# Tastendruckverl_ngerer_1a.net
KiCad netlist of a schematic drawn in EAGLE
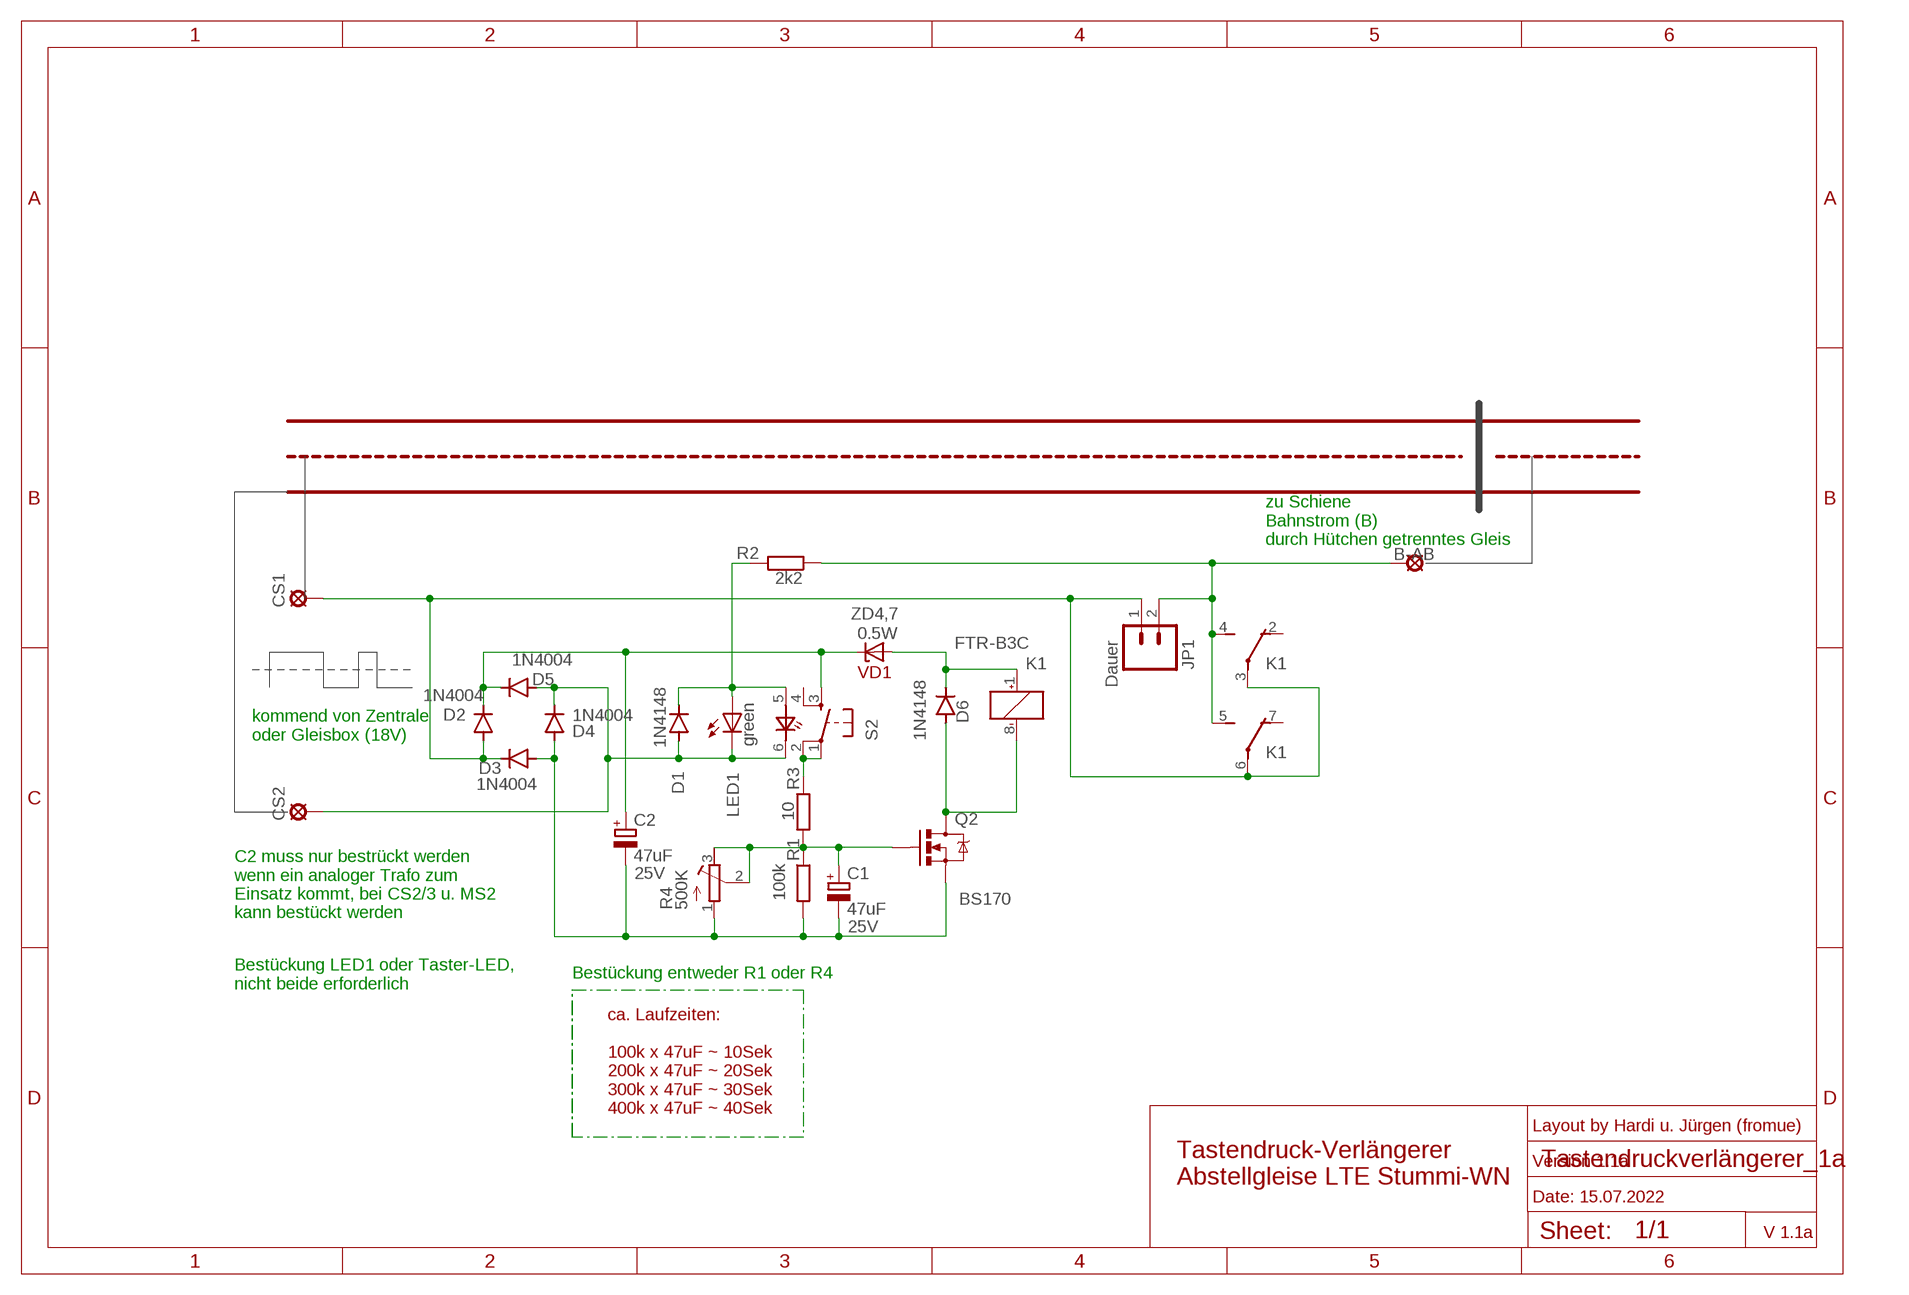
[diagram p0: schematic, sheet 1]

(export (version "E")
  (design (tool "Eeschema 10.0.6"))
  (components
    (comp (ref "B-AB")
      (value "SE14")
      (footprint "eagle-import:SE14")
      (libsource (lib "eagle-import") (part "SE14"))
    )
    (comp (ref "C1")
      (value "47uF")
      (footprint "eagle-import:TT2D5L")
      (fields (field (name "ADD") "25V"))
      (libsource (lib "eagle-import") (part "CPOL-EUTT2D5L"))
    )
    (comp (ref "C2")
      (value "47uF")
      (footprint "eagle-import:TT2D5L")
      (fields (field (name "ADD") "25V"))
      (libsource (lib "eagle-import") (part "CPOL-EUTT2D5L"))
    )
    (comp (ref "CS1")
      (value "SE14")
      (footprint "eagle-import:SE14")
      (libsource (lib "eagle-import") (part "SE14"))
    )
    (comp (ref "CS2")
      (value "SE14")
      (footprint "eagle-import:SE14")
      (libsource (lib "eagle-import") (part "SE14"))
    )
    (comp (ref "D1")
      (value "1N4148")
      (footprint "eagle-import:DO35-7")
      (fields (field (name "SPICEPREFIX") "D"))
      (libsource (lib "eagle-import") (part "1N4148DO35-7"))
    )
    (comp (ref "D2")
      (value "1N4004")
      (footprint "eagle-import:DO41-10A")
      (libsource (lib "eagle-import") (part "1N4004DO41-10A"))
    )
    (comp (ref "D3")
      (value "1N4004")
      (footprint "eagle-import:DO41-10A")
      (libsource (lib "eagle-import") (part "1N4004DO41-10A"))
    )
    (comp (ref "D4")
      (value "1N4004")
      (footprint "eagle-import:DO41-10A")
      (libsource (lib "eagle-import") (part "1N4004DO41-10A"))
    )
    (comp (ref "D5")
      (value "1N4004")
      (footprint "eagle-import:DO41-10A")
      (libsource (lib "eagle-import") (part "1N4004DO41-10A"))
    )
    (comp (ref "D6")
      (value "1N4148")
      (footprint "eagle-import:DO35-7")
      (fields (field (name "SPICEPREFIX") "D"))
      (libsource (lib "eagle-import") (part "1N4148DO35-7"))
    )
    (comp (ref "JP1")
      (value "Dauer")
      (footprint "eagle-import:1X02")
      (libsource (lib "eagle-import") (part "M02PTH"))
    )
    (comp (ref "K1")
      (value "FTR-B3C")
      (footprint "eagle-import:FTR-B4C")
      (libsource (lib "eagle-import") (part "FTR-B3C"))
    )
    (comp (ref "LED1")
      (value "green")
      (footprint "eagle-import:LED3MM")
      (libsource (lib "eagle-import") (part "LED3MM"))
    )
    (comp (ref "Q2")
      (value "BS170")
      (footprint "eagle-import:TO-92")
      (libsource (lib "eagle-import") (part "MOSFET-NCHANNELBS170"))
    )
    (comp (ref "R1")
      (value "100k")
      (footprint "eagle-import:0204_7")
      (libsource (lib "eagle-import") (part "R0204/7"))
    )
    (comp (ref "R2")
      (value "2k2")
      (footprint "eagle-import:0204_7")
      (fields (field (name "SPICEPREFIX") "4k7"))
      (libsource (lib "eagle-import") (part "R0204/7"))
    )
    (comp (ref "R3")
      (value "10")
      (footprint "eagle-import:0204_7")
      (libsource (lib "eagle-import") (part "R0204/7"))
    )
    (comp (ref "R4")
      (value "500K")
      (footprint "eagle-import:RTRIM3296W")
      (libsource (lib "eagle-import") (part "R-TRIMM3296W"))
    )
    (comp (ref "S2")
      (value "TASTER_LEDTC-1198-B")
      (footprint "eagle-import:TASTER_LED")
      (libsource (lib "eagle-import") (part "TASTER_LEDTC-1198-B"))
    )
    (comp (ref "VD1")
      (value "ZD4,7")
      (footprint "eagle-import:DIODES-ZENER_DO35-7")
      (fields (field (name "MOUSER") "ZF4.7") (field (name "POWER") "0.5W"))
      (libsource (lib "eagle-import") (part "DIODES-ZENER_?5.6V(1N5232)"))
    )
  )
  (nets
    (net (code "1") (name "Net-(K1A-P)") (class "Default")
      (node (ref "CS1") (pin "MP") (pinfunction "MP_MP") (pintype "passive"))
      (node (ref "D2") (pin "A") (pinfunction "A_A") (pintype "passive"))
      (node (ref "D3") (pin "C") (pinfunction "C_C") (pintype "passive"))
      (node (ref "JP1") (pin "1") (pinfunction "1_1") (pintype "passive"))
      (node (ref "K1") (pin "3") (pinfunction "P_3") (pintype "passive"))
      (node (ref "K1") (pin "6") (pinfunction "P_6") (pintype "passive"))
    )
    (net (code "2") (name "Net-(K1A-S)") (class "Default")
      (node (ref "B-AB") (pin "MP") (pinfunction "MP_MP") (pintype "passive"))
      (node (ref "JP1") (pin "2") (pinfunction "2_2") (pintype "passive"))
      (node (ref "K1") (pin "4") (pinfunction "S_4") (pintype "passive"))
      (node (ref "K1") (pin "5") (pinfunction "S_5") (pintype "passive"))
      (node (ref "R2") (pin "1") (pinfunction "1_1") (pintype "passive"))
    )
    (net (code "3") (name "Net-(K1C-+)") (class "Default")
      (node (ref "D6") (pin "C") (pinfunction "C_C") (pintype "passive"))
      (node (ref "K1") (pin "1") (pinfunction "+_1") (pintype "passive"))
      (node (ref "VD1") (pin "A") (pinfunction "A_A") (pintype "passive"))
    )
    (net (code "4") (name "Net-(K1C--)") (class "Default")
      (node (ref "D6") (pin "A") (pinfunction "A_A") (pintype "passive"))
      (node (ref "K1") (pin "8") (pinfunction "-_8") (pintype "passive"))
      (node (ref "Q2") (pin "1") (pinfunction "D_1") (pintype "passive"))
    )
    (net (code "5") (name "Net-(LED1-C)") (class "Default")
      (node (ref "CS2") (pin "MP") (pinfunction "MP_MP") (pintype "passive"))
      (node (ref "D1") (pin "A") (pinfunction "A_A") (pintype "passive"))
      (node (ref "D4") (pin "C") (pinfunction "C_C") (pintype "passive"))
      (node (ref "D5") (pin "A") (pinfunction "A_A") (pintype "passive"))
      (node (ref "LED1") (pin "K") (pinfunction "C_K") (pintype "passive"))
      (node (ref "S2") (pin "6") (pinfunction "-_6") (pintype "input"))
    )
    (net (code "6") (name "Net-(Q2-G)") (class "Default")
      (node (ref "C1") (pin "+") (pinfunction "+_+") (pintype "passive"))
      (node (ref "Q2") (pin "2") (pinfunction "G_2") (pintype "passive"))
      (node (ref "R1") (pin "1") (pinfunction "1_1") (pintype "passive"))
      (node (ref "R3") (pin "2") (pinfunction "2_2") (pintype "passive"))
      (node (ref "R4") (pin "2") (pinfunction "S_2") (pintype "passive"))
      (node (ref "R4") (pin "3") (pinfunction "E_3") (pintype "passive"))
    )
    (net (code "7") (name "Net-(Q2-S)") (class "Default")
      (node (ref "C1") (pin "-") (pinfunction "-_-") (pintype "passive"))
      (node (ref "C2") (pin "-") (pinfunction "-_-") (pintype "passive"))
      (node (ref "D3") (pin "A") (pinfunction "A_A") (pintype "passive"))
      (node (ref "D4") (pin "A") (pinfunction "A_A") (pintype "passive"))
      (node (ref "Q2") (pin "3") (pinfunction "S_3") (pintype "passive"))
      (node (ref "R1") (pin "2") (pinfunction "2_2") (pintype "passive"))
      (node (ref "R4") (pin "1") (pinfunction "A_1") (pintype "passive"))
    )
    (net (code "8") (name "Net-(S2-+)") (class "Default")
      (node (ref "D1") (pin "C") (pinfunction "C_C") (pintype "passive"))
      (node (ref "LED1") (pin "A") (pinfunction "A_A") (pintype "passive"))
      (node (ref "R2") (pin "2") (pinfunction "2_2") (pintype "passive"))
      (node (ref "S2") (pin "5") (pinfunction "+_5") (pintype "input"))
    )
    (net (code "9") (name "Net-(S2-P)") (class "Default")
      (node (ref "R3") (pin "1") (pinfunction "1_1") (pintype "passive"))
      (node (ref "S2") (pin "1") (pinfunction "P_1") (pintype "passive"))
      (node (ref "S2") (pin "2") (pinfunction "P1_2") (pintype "passive"))
    )
    (net (code "10") (name "Net-(S2-S)") (class "Default")
      (node (ref "C2") (pin "+") (pinfunction "+_+") (pintype "passive"))
      (node (ref "D2") (pin "C") (pinfunction "C_C") (pintype "passive"))
      (node (ref "D5") (pin "C") (pinfunction "C_C") (pintype "passive"))
      (node (ref "S2") (pin "3") (pinfunction "S_3") (pintype "passive"))
      (node (ref "VD1") (pin "C") (pinfunction "C_C") (pintype "passive"))
    )
    (net (code "11") (name "unconnected-(K1A-O-Pad2)") (class "Default")
      (node (ref "K1") (pin "2") (pinfunction "O_2") (pintype "passive"))
    )
    (net (code "12") (name "unconnected-(K1B-O-Pad7)") (class "Default")
      (node (ref "K1") (pin "7") (pinfunction "O_7") (pintype "passive"))
    )
    (net (code "13") (name "unconnected-(S2-S1-Pad4)") (class "Default")
      (node (ref "S2") (pin "4") (pinfunction "S1_4") (pintype "passive"))
    )
  )
)
